# Sheet3.net
KiCad netlist of a schematic drawn in Altium Designer
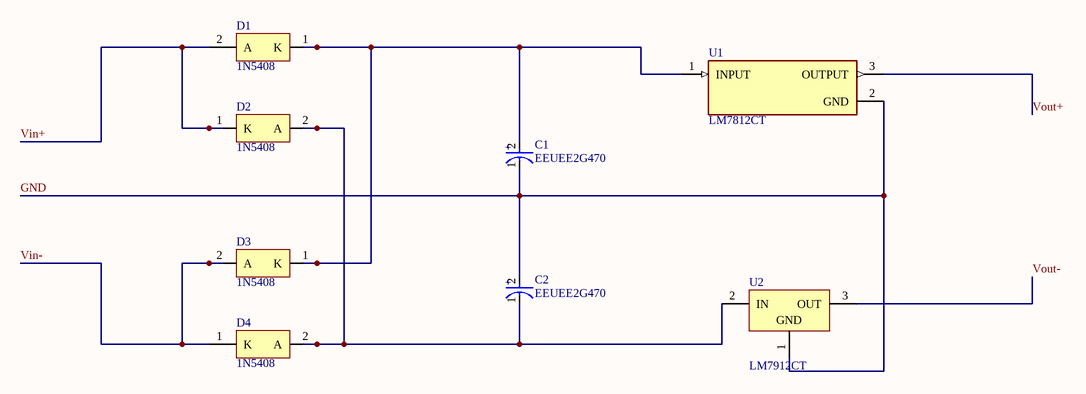
[diagram p0: Sheet3.SchDoc]

(export (version "E")
  (design (tool "Eeschema 10.0.6"))
  (components
    (comp (ref "C1")
      (value "EEUEE2G470")
      (footprint "FP-RAD-TH-D_16_0_5-L_25_2-MFG")
      (description "Aluminum Electrolytic Capacitors (Radial Lead Type) 47uF ±20% 400V")
      (fields (field (name "VOLTAGE") "400V") (field (name "TOLERANCE") "20%"))
      (libsource (lib "Altium Content Vault") (part "203bc49f2ac43e59fd269a8c329ed05"))
    )
    (comp (ref "C2")
      (value "EEUEE2G470")
      (footprint "FP-RAD-TH-D_16_0_5-L_25_2-MFG")
      (description "Aluminum Electrolytic Capacitors (Radial Lead Type) 47uF ±20% 400V")
      (fields (field (name "VOLTAGE") "400V") (field (name "TOLERANCE") "20%"))
      (libsource (lib "Altium Content Vault") (part "203bc49f2ac43e59fd269a8c329ed05"))
    )
    (comp (ref "D1")
      (value "1N5408")
      (footprint "ONSC-AXIAL_LEAD-2-267-05_V")
      (description "Standard Recovery Rectifier, 2-Pin Axial_Lead, Pb-Free, Bulk Box")
      (fields (field (name "MANUFACTURER") "On Semiconductor"))
      (libsource (lib "") (part "ONSC-D-K1A2-2_A_1"))
    )
    (comp (ref "D2")
      (value "1N5408")
      (footprint "ONSC-AXIAL_LEAD-2-267-05_V")
      (description "Standard Recovery Rectifier, 2-Pin Axial_Lead, Pb-Free, Bulk Box")
      (fields (field (name "MANUFACTURER") "On Semiconductor"))
      (libsource (lib "Altium Content Vault") (part "ONSC-D-K1A2-2_A"))
    )
    (comp (ref "D3")
      (value "1N5408")
      (footprint "ONSC-AXIAL_LEAD-2-267-05_V")
      (description "Standard Recovery Rectifier, 2-Pin Axial_Lead, Pb-Free, Bulk Box")
      (fields (field (name "MANUFACTURER") "On Semiconductor"))
      (libsource (lib "") (part "ONSC-D-K1A2-2_A_1"))
    )
    (comp (ref "D4")
      (value "1N5408")
      (footprint "ONSC-AXIAL_LEAD-2-267-05_V")
      (description "Standard Recovery Rectifier, 2-Pin Axial_Lead, Pb-Free, Bulk Box")
      (fields (field (name "MANUFACTURER") "On Semiconductor"))
      (libsource (lib "Altium Content Vault") (part "ONSC-D-K1A2-2_A"))
    )
    (comp (ref "U1")
      (value "LM7812CT")
      (footprint "FP-TO220B03-MFG")
      (description "IC REG LINEAR 12V 1A TO220-3")
      (fields
        (field (name "OCTOPART") "https://octopart.com/lm7812ct-on+semiconductor-14383031")
        (field (name "OBSOLETE PART") "true")
      )
      (libsource (lib "Altium Content Vault") (part "6207a8f1a6b4db326a9e0a8a99b4969"))
    )
    (comp (ref "U2")
      (value "LM7912CT")
      (footprint "NDE0003A")
      (description "3-Terminal Negative Regulator, 3-pin TO-220")
      (fields (field (name "MANUFACTURER") "Texas Instruments"))
      (libsource (lib "Altium Content Vault") (part "PM-REG-LM7905-SIL3"))
    )
  )
  (nets
    (net (code "1") (name "/GND") (class "Default")
      (node (ref "C1") (pin "1") (pinfunction "C_1") (pintype "passive"))
      (node (ref "C2") (pin "2") (pinfunction "A_2") (pintype "passive"))
      (node (ref "U1") (pin "2") (pinfunction "GND_2") (pintype "power_in"))
      (node (ref "U2") (pin "1") (pinfunction "GND_1") (pintype "power_in"))
    )
    (net (code "2") (name "/Vin+") (class "Default")
      (node (ref "D1") (pin "2") (pinfunction "A_2") (pintype "passive"))
      (node (ref "D2") (pin "1") (pinfunction "K_1") (pintype "passive"))
    )
    (net (code "3") (name "/Vin-") (class "Default")
      (node (ref "D3") (pin "2") (pinfunction "A_2") (pintype "passive"))
      (node (ref "D4") (pin "1") (pinfunction "K_1") (pintype "passive"))
    )
    (net (code "4") (name "/Vout+") (class "Default")
      (node (ref "U1") (pin "3") (pinfunction "OUTPUT_3") (pintype "output"))
    )
    (net (code "5") (name "/Vout-") (class "Default")
      (node (ref "U2") (pin "3") (pinfunction "OUT_3") (pintype "power_in"))
    )
    (net (code "6") (name "Net-(C1-A)") (class "Default")
      (node (ref "C1") (pin "2") (pinfunction "A_2") (pintype "passive"))
      (node (ref "D1") (pin "1") (pinfunction "K_1") (pintype "passive"))
      (node (ref "D3") (pin "1") (pinfunction "K_1") (pintype "passive"))
      (node (ref "U1") (pin "1") (pinfunction "INPUT_1") (pintype "input"))
    )
    (net (code "7") (name "Net-(C2-C)") (class "Default")
      (node (ref "C2") (pin "1") (pinfunction "C_1") (pintype "passive"))
      (node (ref "D2") (pin "2") (pinfunction "A_2") (pintype "passive"))
      (node (ref "D4") (pin "2") (pinfunction "A_2") (pintype "passive"))
      (node (ref "U2") (pin "2") (pinfunction "IN_2") (pintype "power_in"))
    )
  )
)
